# riser-extender.net
KiCad netlist of a schematic drawn in EAGLE
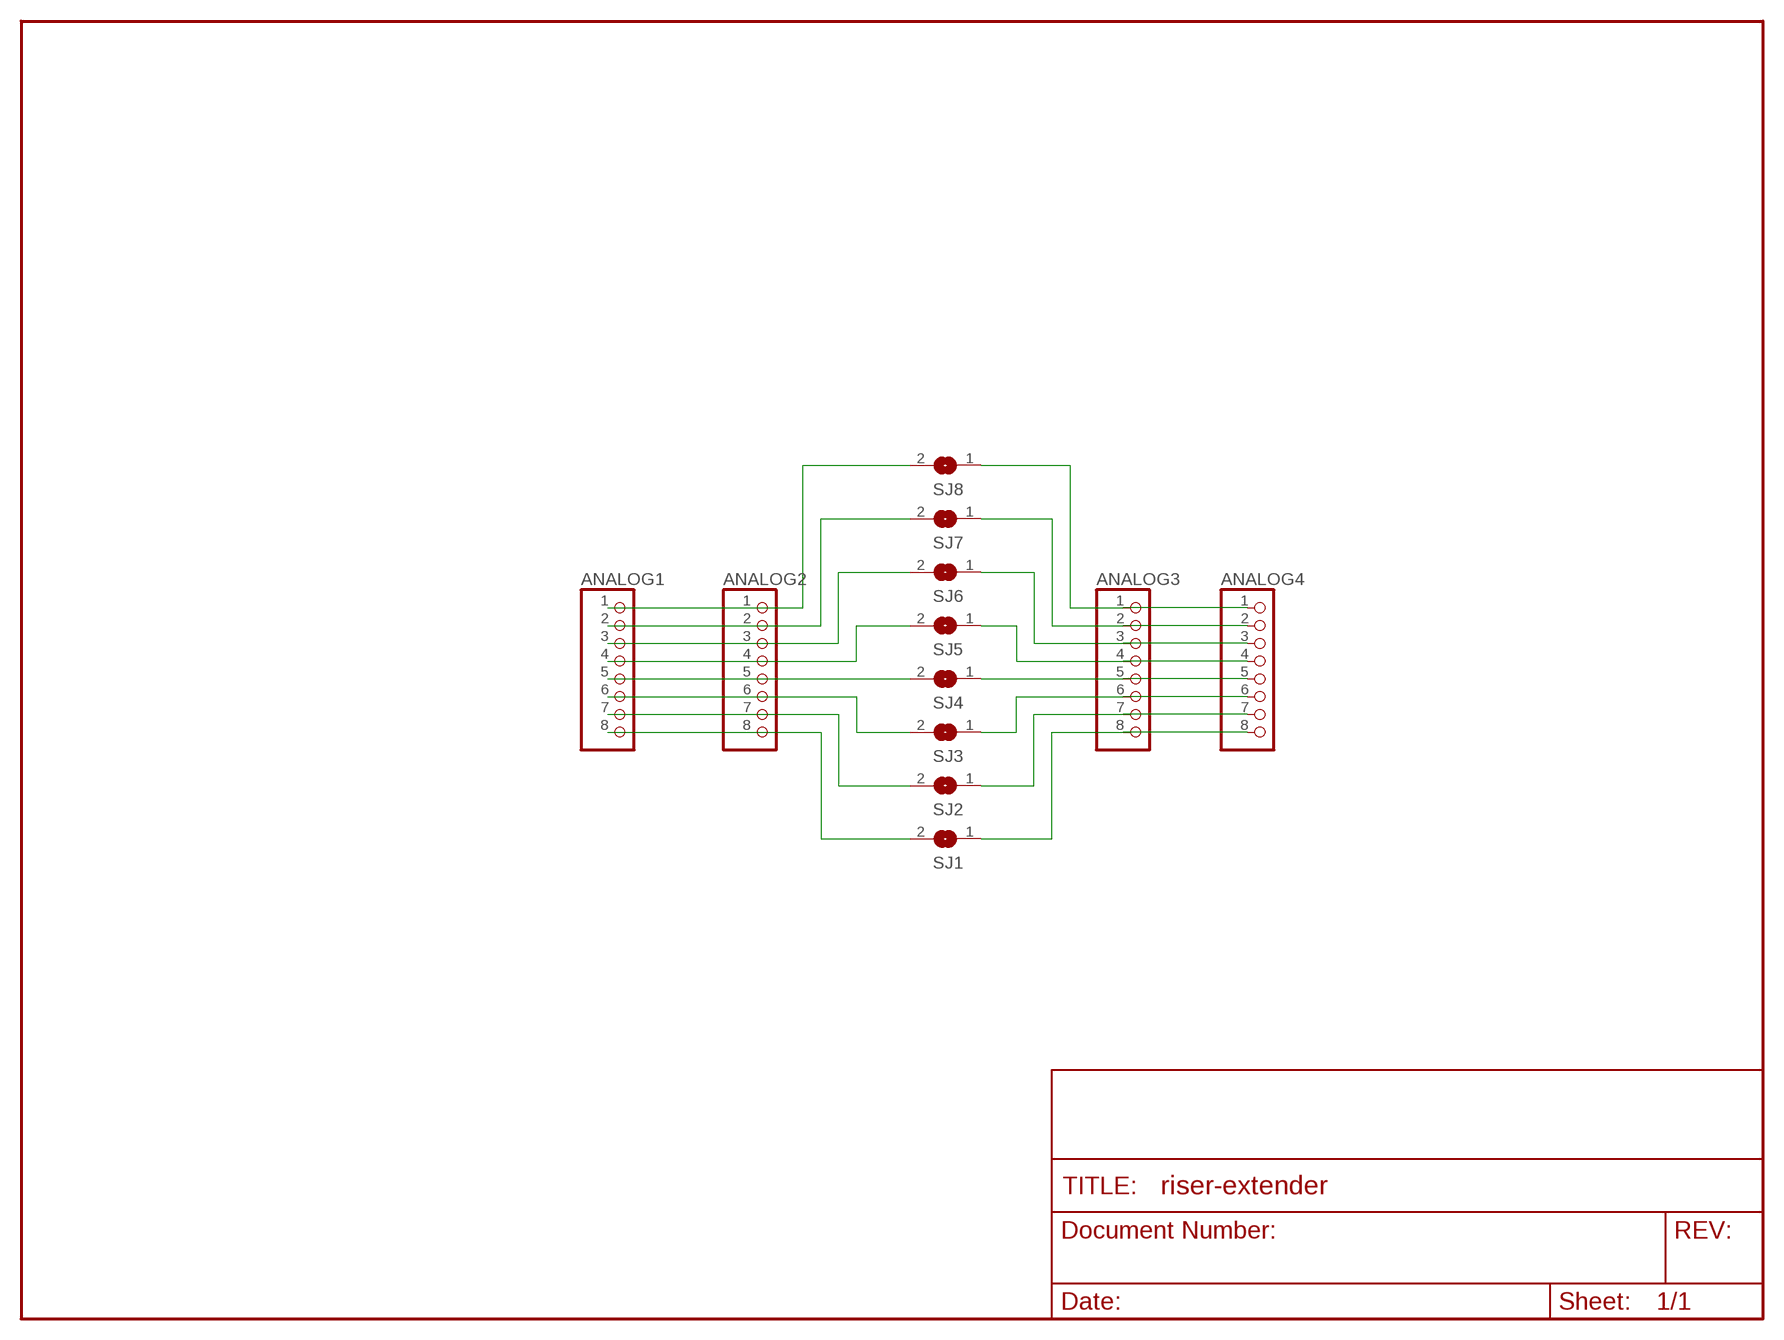
[diagram p0: schematic, sheet 1]

(export (version "E")
  (design (tool "Eeschema 10.0.6"))
  (components
    (comp (ref "ANALOG1")
      (value "PINHD-1X8")
      (footprint "eagle-import:1X08")
      (libsource (lib "eagle-import") (part "PINHD-1X8"))
    )
    (comp (ref "ANALOG2")
      (value "PINHD-1X8")
      (footprint "eagle-import:1X08")
      (libsource (lib "eagle-import") (part "PINHD-1X8"))
    )
    (comp (ref "ANALOG3")
      (value "PINHD-1X8")
      (footprint "eagle-import:1X08")
      (libsource (lib "eagle-import") (part "PINHD-1X8"))
    )
    (comp (ref "ANALOG4")
      (value "PINHD-1X8")
      (footprint "eagle-import:1X08")
      (libsource (lib "eagle-import") (part "PINHD-1X8"))
    )
    (comp (ref "SJ1") (value "SJ") (footprint "eagle-import:SJ") (libsource (lib "eagle-import") (part "SJ")))
    (comp (ref "SJ2") (value "SJ") (footprint "eagle-import:SJ") (libsource (lib "eagle-import") (part "SJ")))
    (comp (ref "SJ3") (value "SJ") (footprint "eagle-import:SJ") (libsource (lib "eagle-import") (part "SJ")))
    (comp (ref "SJ4") (value "SJ") (footprint "eagle-import:SJ") (libsource (lib "eagle-import") (part "SJ")))
    (comp (ref "SJ5") (value "SJ") (footprint "eagle-import:SJ") (libsource (lib "eagle-import") (part "SJ")))
    (comp (ref "SJ6") (value "SJ") (footprint "eagle-import:SJ") (libsource (lib "eagle-import") (part "SJ")))
    (comp (ref "SJ7") (value "SJ") (footprint "eagle-import:SJ") (libsource (lib "eagle-import") (part "SJ")))
    (comp (ref "SJ8") (value "SJ") (footprint "eagle-import:SJ") (libsource (lib "eagle-import") (part "SJ")))
  )
  (nets
    (net (code "1") (name "Net-(ANALOG1-Pad1)") (class "Default")
      (node (ref "ANALOG1") (pin "1") (pinfunction "1_1") (pintype "passive"))
      (node (ref "ANALOG2") (pin "1") (pinfunction "1_1") (pintype "passive"))
      (node (ref "SJ8") (pin "2") (pinfunction "2_2") (pintype "passive"))
    )
    (net (code "2") (name "Net-(ANALOG1-Pad2)") (class "Default")
      (node (ref "ANALOG1") (pin "2") (pinfunction "2_2") (pintype "passive"))
      (node (ref "ANALOG2") (pin "2") (pinfunction "2_2") (pintype "passive"))
      (node (ref "SJ7") (pin "2") (pinfunction "2_2") (pintype "passive"))
    )
    (net (code "3") (name "Net-(ANALOG1-Pad3)") (class "Default")
      (node (ref "ANALOG1") (pin "3") (pinfunction "3_3") (pintype "passive"))
      (node (ref "ANALOG2") (pin "3") (pinfunction "3_3") (pintype "passive"))
      (node (ref "SJ6") (pin "2") (pinfunction "2_2") (pintype "passive"))
    )
    (net (code "4") (name "Net-(ANALOG1-Pad4)") (class "Default")
      (node (ref "ANALOG1") (pin "4") (pinfunction "4_4") (pintype "passive"))
      (node (ref "ANALOG2") (pin "4") (pinfunction "4_4") (pintype "passive"))
      (node (ref "SJ5") (pin "2") (pinfunction "2_2") (pintype "passive"))
    )
    (net (code "5") (name "Net-(ANALOG1-Pad5)") (class "Default")
      (node (ref "ANALOG1") (pin "5") (pinfunction "5_5") (pintype "passive"))
      (node (ref "ANALOG2") (pin "5") (pinfunction "5_5") (pintype "passive"))
      (node (ref "SJ4") (pin "2") (pinfunction "2_2") (pintype "passive"))
    )
    (net (code "6") (name "Net-(ANALOG1-Pad6)") (class "Default")
      (node (ref "ANALOG1") (pin "6") (pinfunction "6_6") (pintype "passive"))
      (node (ref "ANALOG2") (pin "6") (pinfunction "6_6") (pintype "passive"))
      (node (ref "SJ3") (pin "2") (pinfunction "2_2") (pintype "passive"))
    )
    (net (code "7") (name "Net-(ANALOG1-Pad7)") (class "Default")
      (node (ref "ANALOG1") (pin "7") (pinfunction "7_7") (pintype "passive"))
      (node (ref "ANALOG2") (pin "7") (pinfunction "7_7") (pintype "passive"))
      (node (ref "SJ2") (pin "2") (pinfunction "2_2") (pintype "passive"))
    )
    (net (code "8") (name "Net-(ANALOG1-Pad8)") (class "Default")
      (node (ref "ANALOG1") (pin "8") (pinfunction "8_8") (pintype "passive"))
      (node (ref "ANALOG2") (pin "8") (pinfunction "8_8") (pintype "passive"))
      (node (ref "SJ1") (pin "2") (pinfunction "2_2") (pintype "passive"))
    )
    (net (code "9") (name "Net-(ANALOG3-Pad1)") (class "Default")
      (node (ref "ANALOG3") (pin "1") (pinfunction "1_1") (pintype "passive"))
      (node (ref "ANALOG4") (pin "1") (pinfunction "1_1") (pintype "passive"))
      (node (ref "SJ8") (pin "1") (pinfunction "1_1") (pintype "passive"))
    )
    (net (code "10") (name "Net-(ANALOG3-Pad2)") (class "Default")
      (node (ref "ANALOG3") (pin "2") (pinfunction "2_2") (pintype "passive"))
      (node (ref "ANALOG4") (pin "2") (pinfunction "2_2") (pintype "passive"))
      (node (ref "SJ7") (pin "1") (pinfunction "1_1") (pintype "passive"))
    )
    (net (code "11") (name "Net-(ANALOG3-Pad3)") (class "Default")
      (node (ref "ANALOG3") (pin "3") (pinfunction "3_3") (pintype "passive"))
      (node (ref "ANALOG4") (pin "3") (pinfunction "3_3") (pintype "passive"))
      (node (ref "SJ6") (pin "1") (pinfunction "1_1") (pintype "passive"))
    )
    (net (code "12") (name "Net-(ANALOG3-Pad4)") (class "Default")
      (node (ref "ANALOG3") (pin "4") (pinfunction "4_4") (pintype "passive"))
      (node (ref "ANALOG4") (pin "4") (pinfunction "4_4") (pintype "passive"))
      (node (ref "SJ5") (pin "1") (pinfunction "1_1") (pintype "passive"))
    )
    (net (code "13") (name "Net-(ANALOG3-Pad5)") (class "Default")
      (node (ref "ANALOG3") (pin "5") (pinfunction "5_5") (pintype "passive"))
      (node (ref "ANALOG4") (pin "5") (pinfunction "5_5") (pintype "passive"))
      (node (ref "SJ4") (pin "1") (pinfunction "1_1") (pintype "passive"))
    )
    (net (code "14") (name "Net-(ANALOG3-Pad6)") (class "Default")
      (node (ref "ANALOG3") (pin "6") (pinfunction "6_6") (pintype "passive"))
      (node (ref "ANALOG4") (pin "6") (pinfunction "6_6") (pintype "passive"))
      (node (ref "SJ3") (pin "1") (pinfunction "1_1") (pintype "passive"))
    )
    (net (code "15") (name "Net-(ANALOG3-Pad7)") (class "Default")
      (node (ref "ANALOG3") (pin "7") (pinfunction "7_7") (pintype "passive"))
      (node (ref "ANALOG4") (pin "7") (pinfunction "7_7") (pintype "passive"))
      (node (ref "SJ2") (pin "1") (pinfunction "1_1") (pintype "passive"))
    )
    (net (code "16") (name "Net-(ANALOG3-Pad8)") (class "Default")
      (node (ref "ANALOG3") (pin "8") (pinfunction "8_8") (pintype "passive"))
      (node (ref "ANALOG4") (pin "8") (pinfunction "8_8") (pintype "passive"))
      (node (ref "SJ1") (pin "1") (pinfunction "1_1") (pintype "passive"))
    )
  )
)
